# Sheet1.net
KiCad netlist of a schematic drawn in Altium Designer
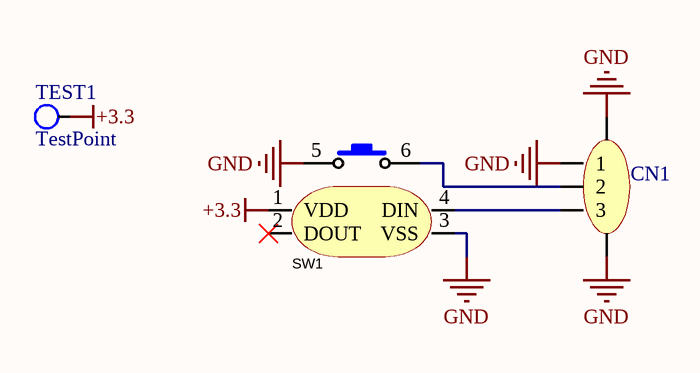
[diagram p0: Sheet1.SchDoc]

(export (version "E")
  (design (tool "Eeschema 10.0.6"))
  (components
    (comp (ref "CN1")
      (value "HDGC1002WR-S-3P")
      (footprint "SH1.0_3P")
      (fields (field (name "MANUFACTURER") "HDGC(华德共创)"))
      (libsource (lib "Connector") (part "3P端子"))
    )
    (comp (ref "SW1")
      (value "佳达隆带灯热插拔矮轴")
      (footprint "Gateron_Switch_Direct")
      (libsource (lib "Switch") (part "Gateron_Switch_Low"))
    )
    (comp (ref "TEST1")
      (value "TestPoint")
      (footprint "TestPoint_0402")
      (libsource (lib "RC") (part "TestPoint"))
    )
  )
  (nets
    (net (code "1") (name "+3.3") (class "Default")
      (node (ref "SW1") (pin "1") (pinfunction "VDD_1") (pintype "passive"))
      (node (ref "TEST1") (pin "1") (pinfunction "1_1") (pintype "passive"))
    )
    (net (code "2") (name "GND") (class "Default")
      (node (ref "CN1") (pin "1") (pinfunction "1_1") (pintype "passive"))
      (node (ref "CN1") (pin "4") (pinfunction "4_4") (pintype "passive"))
      (node (ref "CN1") (pin "5") (pinfunction "5_5") (pintype "passive"))
      (node (ref "SW1") (pin "3") (pinfunction "VSS_3") (pintype "passive"))
      (node (ref "SW1") (pin "5") (pinfunction "1_5") (pintype "passive"))
    )
    (net (code "3") (name "Net-(SW1-2)") (class "Default")
      (node (ref "CN1") (pin "2") (pinfunction "2_2") (pintype "passive"))
      (node (ref "SW1") (pin "6") (pinfunction "2_6") (pintype "passive"))
    )
    (net (code "4") (name "Net-(SW1-DIN)") (class "Default")
      (node (ref "CN1") (pin "3") (pinfunction "3_3") (pintype "passive"))
      (node (ref "SW1") (pin "4") (pinfunction "DIN_4") (pintype "passive"))
    )
    (net (code "5") (name "unconnected-(SW1-DOUT-Pad2)") (class "Default")
      (node (ref "SW1") (pin "2") (pinfunction "DOUT_2") (pintype "passive+no_connect"))
    )
  )
)
